# Reflow_triac_page1.net
KiCad netlist of a schematic drawn in EAGLE
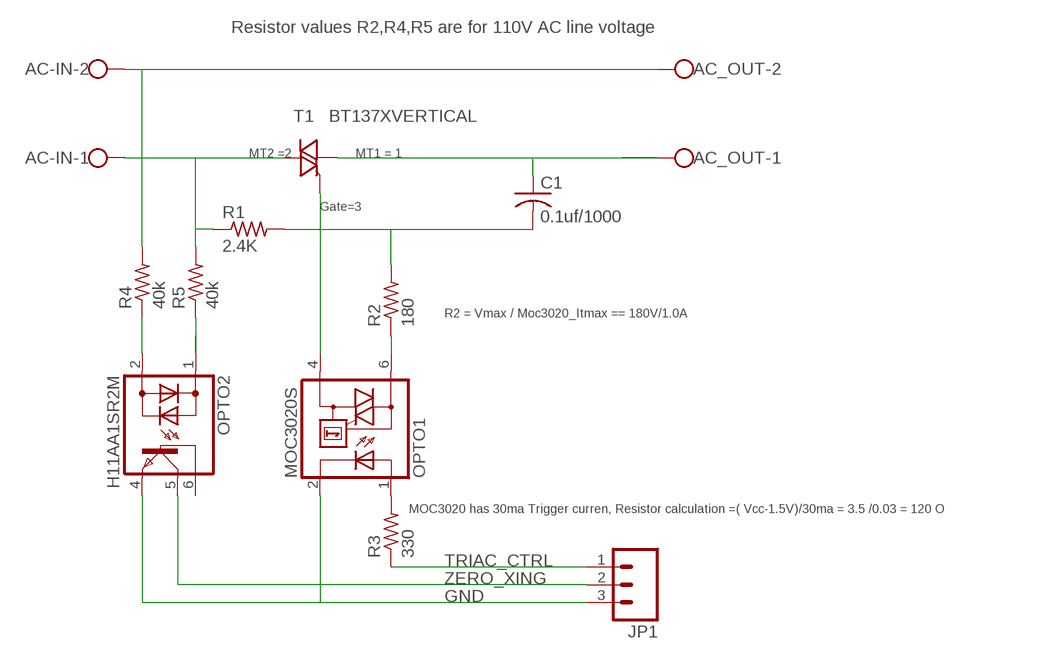
[diagram p0: schematic, sheet 1]

(export (version "E")
  (design (tool "Eeschema 10.0.6"))
  (components
    (comp (ref "AC-IN")
      (value "W237-102")
      (footprint "eagle-import:W237-102")
      (fields (field (name "MPN") "237-102"))
      (libsource (lib "eagle-import") (part "W237-102"))
    )
    (comp (ref "AC_OUT")
      (value "W237-102")
      (footprint "eagle-import:W237-102")
      (fields (field (name "MPN") "237-102"))
      (libsource (lib "eagle-import") (part "W237-102"))
    )
    (comp (ref "C1")
      (value "0.1uf/1000")
      (footprint "eagle-import:C102_152-062X184")
      (libsource (lib "eagle-import") (part "C-US102_152-062X184"))
    )
    (comp (ref "JP1")
      (value "M03PTH")
      (footprint "eagle-import:1X03")
      (libsource (lib "eagle-import") (part "M03PTH"))
    )
    (comp (ref "OPTO1")
      (value "MOC3020S")
      (footprint "eagle-import:DIL6-SMD")
      (libsource (lib "eagle-import") (part "MOC30MSMD"))
    )
    (comp (ref "OPTO2")
      (value "H11AA1SR2M")
      (footprint "eagle-import:DIL6-SMD")
      (libsource (lib "eagle-import") (part "IL250SMD"))
    )
    (comp (ref "R1")
      (value "2.4K")
      (footprint "eagle-import:0207_10")
      (libsource (lib "eagle-import") (part "R-US_0207/10"))
    )
    (comp (ref "R2")
      (value "180")
      (footprint "eagle-import:0207_10")
      (libsource (lib "eagle-import") (part "R-US_0207/10"))
    )
    (comp (ref "R3")
      (value "330")
      (footprint "eagle-import:0207_10")
      (libsource (lib "eagle-import") (part "R-US_0207/10"))
    )
    (comp (ref "R4")
      (value "40k")
      (footprint "eagle-import:0207_10")
      (libsource (lib "eagle-import") (part "R-US_0207/10"))
    )
    (comp (ref "R5")
      (value "40k")
      (footprint "eagle-import:0207_10")
      (libsource (lib "eagle-import") (part "R-US_0207/10"))
    )
    (comp (ref "T1")
      (value "BT137XVERTICAL")
      (footprint "eagle-import:TO220DS")
      (libsource (lib "eagle-import") (part "BT137XVERTICAL"))
    )
  )
  (nets
    (net (code "1") (name "/GND") (class "Default")
      (node (ref "JP1") (pin "3") (pinfunction "3_3") (pintype "passive"))
      (node (ref "OPTO1") (pin "2") (pinfunction "C_2") (pintype "passive"))
      (node (ref "OPTO2") (pin "4") (pinfunction "E_4") (pintype "passive"))
    )
    (net (code "2") (name "/TRIAC_CTRL") (class "Default")
      (node (ref "JP1") (pin "1") (pinfunction "1_1") (pintype "passive"))
      (node (ref "R3") (pin "1") (pinfunction "1_1") (pintype "passive"))
    )
    (net (code "3") (name "/ZERO_XING") (class "Default")
      (node (ref "JP1") (pin "2") (pinfunction "2_2") (pintype "passive"))
      (node (ref "OPTO2") (pin "5") (pinfunction "C_5") (pintype "passive"))
    )
    (net (code "4") (name "Net-(AC-INA-KL)") (class "Default")
      (node (ref "AC-IN") (pin "1") (pinfunction "KL_1") (pintype "passive"))
      (node (ref "R1") (pin "1") (pinfunction "1_1") (pintype "passive"))
      (node (ref "R5") (pin "2") (pinfunction "2_2") (pintype "passive"))
      (node (ref "T1") (pin "A2") (pinfunction "A2_A2") (pintype "passive"))
    )
    (net (code "5") (name "Net-(AC-INB-KL)") (class "Default")
      (node (ref "AC-IN") (pin "2") (pinfunction "KL_2") (pintype "passive"))
      (node (ref "AC_OUT") (pin "2") (pinfunction "KL_2") (pintype "passive"))
      (node (ref "R4") (pin "2") (pinfunction "2_2") (pintype "passive"))
    )
    (net (code "6") (name "Net-(AC_OUTA-KL)") (class "Default")
      (node (ref "AC_OUT") (pin "1") (pinfunction "KL_1") (pintype "passive"))
      (node (ref "C1") (pin "1") (pinfunction "1_1") (pintype "passive"))
      (node (ref "T1") (pin "A1") (pinfunction "A1_A1") (pintype "passive"))
    )
    (net (code "7") (name "Net-(C1-Pad2)") (class "Default")
      (node (ref "C1") (pin "2") (pinfunction "2_2") (pintype "passive"))
      (node (ref "R1") (pin "2") (pinfunction "2_2") (pintype "passive"))
      (node (ref "R2") (pin "2") (pinfunction "2_2") (pintype "passive"))
    )
    (net (code "8") (name "Net-(OPTO1-A)") (class "Default")
      (node (ref "OPTO1") (pin "1") (pinfunction "A_1") (pintype "passive"))
      (node (ref "R3") (pin "2") (pinfunction "2_2") (pintype "passive"))
    )
    (net (code "9") (name "Net-(OPTO1-A1)") (class "Default")
      (node (ref "OPTO1") (pin "4") (pinfunction "A1_4") (pintype "passive"))
      (node (ref "T1") (pin "G") (pinfunction "G_G") (pintype "passive"))
    )
    (net (code "10") (name "Net-(OPTO1-A2)") (class "Default")
      (node (ref "OPTO1") (pin "6") (pinfunction "A2_6") (pintype "passive"))
      (node (ref "R2") (pin "1") (pinfunction "1_1") (pintype "passive"))
    )
    (net (code "11") (name "Net-(OPTO2-AC1)") (class "Default")
      (node (ref "OPTO2") (pin "1") (pinfunction "AC1_1") (pintype "passive"))
      (node (ref "R5") (pin "1") (pinfunction "1_1") (pintype "passive"))
    )
    (net (code "12") (name "Net-(OPTO2-AC2)") (class "Default")
      (node (ref "OPTO2") (pin "2") (pinfunction "AC2_2") (pintype "passive"))
      (node (ref "R4") (pin "1") (pinfunction "1_1") (pintype "passive"))
    )
    (net (code "13") (name "unconnected-(OPTO2-B-Pad6)") (class "Default")
      (node (ref "OPTO2") (pin "6") (pinfunction "B_6") (pintype "passive"))
    )
  )
)
